# sprite.net
KiCad netlist of a schematic drawn in EAGLE
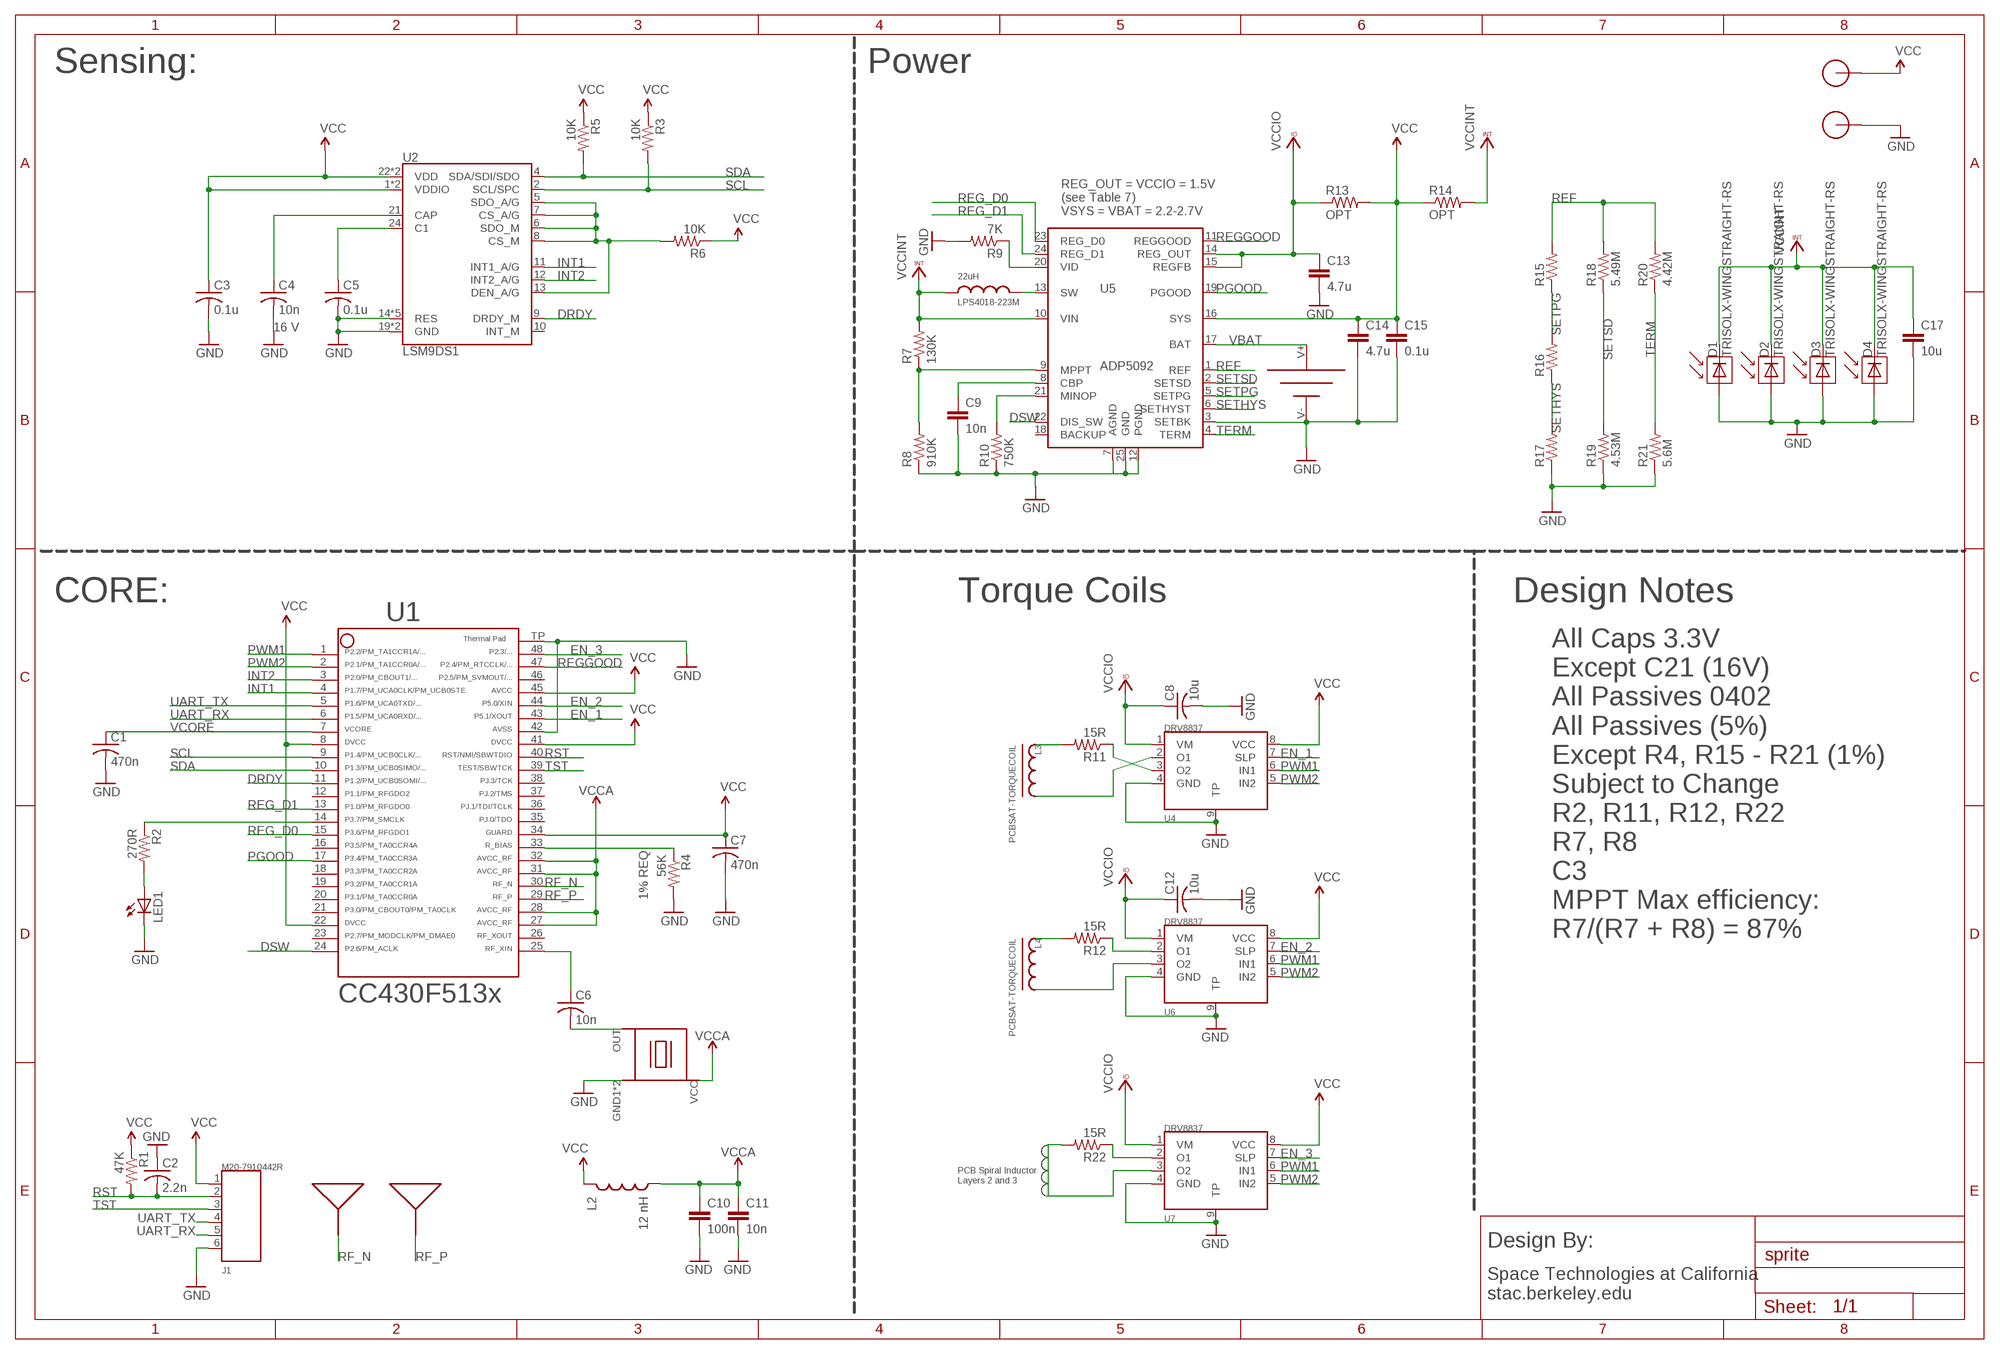
[diagram p0: schematic, sheet 1]

(export (version "E")
  (design (tool "Eeschema 10.0.6"))
  (components
    (comp (ref "A1")
      (value "SPRITEANTENNA_ANTENNA")
      (footprint "eagle-import:SPRITEANTENNA_ANTENNA")
      (libsource (lib "eagle-import") (part "SPRITEANTENNA_ANTENNA"))
    )
    (comp (ref "A2")
      (value "SPRITEANTENNA_ANTENNA")
      (footprint "eagle-import:SPRITEANTENNA_ANTENNA")
      (libsource (lib "eagle-import") (part "SPRITEANTENNA_ANTENNA"))
    )
    (comp (ref "B1")
      (value "UMAC_UMAC")
      (footprint "eagle-import:UMAC_UMAC")
      (libsource (lib "eagle-import") (part "UMAC_UMAC"))
    )
    (comp (ref "C1")
      (value "470n")
      (footprint "eagle-import:C0402")
      (libsource (lib "eagle-import") (part "C-USC0402"))
    )
    (comp (ref "C2")
      (value "2.2n")
      (footprint "eagle-import:C0402")
      (libsource (lib "eagle-import") (part "C-USC0402"))
    )
    (comp (ref "C3")
      (value "0.1u")
      (footprint "eagle-import:C0402")
      (libsource (lib "eagle-import") (part "C-USC0402"))
    )
    (comp (ref "C4")
      (value "10n")
      (footprint "eagle-import:C0402")
      (libsource (lib "eagle-import") (part "C-USC0402"))
    )
    (comp (ref "C5")
      (value "0.1u")
      (footprint "eagle-import:C0402")
      (libsource (lib "eagle-import") (part "C-USC0402"))
    )
    (comp (ref "C6")
      (value "10n")
      (footprint "eagle-import:C0402")
      (libsource (lib "eagle-import") (part "C-USC0402"))
    )
    (comp (ref "C7")
      (value "470n")
      (footprint "eagle-import:C0402")
      (libsource (lib "eagle-import") (part "C-USC0402"))
    )
    (comp (ref "C8")
      (value "10u")
      (footprint "eagle-import:C0402")
      (libsource (lib "eagle-import") (part "C-USC0402"))
    )
    (comp (ref "C9")
      (value "10n")
      (footprint "eagle-import:C0402")
      (libsource (lib "eagle-import") (part "C-EUC0402"))
    )
    (comp (ref "C10")
      (value "100n")
      (footprint "eagle-import:C0402")
      (libsource (lib "eagle-import") (part "C-EUC0402"))
    )
    (comp (ref "C11")
      (value "10n")
      (footprint "eagle-import:C0402")
      (libsource (lib "eagle-import") (part "C-EUC0402"))
    )
    (comp (ref "C12")
      (value "10u")
      (footprint "eagle-import:C0402")
      (libsource (lib "eagle-import") (part "C-USC0402"))
    )
    (comp (ref "C13")
      (value "4.7u")
      (footprint "eagle-import:C0402")
      (libsource (lib "eagle-import") (part "C-EUC0402"))
    )
    (comp (ref "C14")
      (value "4.7u")
      (footprint "eagle-import:C0402")
      (libsource (lib "eagle-import") (part "C-EUC0402"))
    )
    (comp (ref "C15")
      (value "0.1u")
      (footprint "eagle-import:C0402")
      (libsource (lib "eagle-import") (part "C-EUC0402"))
    )
    (comp (ref "C17")
      (value "10u")
      (footprint "eagle-import:C0402")
      (libsource (lib "eagle-import") (part "C-EUC0402"))
    )
    (comp (ref "D1")
      (value "TRISOLX-WINGSTRAIGHT-RS")
      (footprint "eagle-import:TRISOLX-STRAIGHT-RS")
      (libsource (lib "eagle-import") (part "TRISOLX-WINGSTRAIGHT-RS"))
    )
    (comp (ref "D2")
      (value "TRISOLX-WINGSTRAIGHT-RS")
      (footprint "eagle-import:TRISOLX-STRAIGHT-RS")
      (libsource (lib "eagle-import") (part "TRISOLX-WINGSTRAIGHT-RS"))
    )
    (comp (ref "D3")
      (value "TRISOLX-WINGSTRAIGHT-RS")
      (footprint "eagle-import:TRISOLX-STRAIGHT-RS")
      (libsource (lib "eagle-import") (part "TRISOLX-WINGSTRAIGHT-RS"))
    )
    (comp (ref "D4")
      (value "TRISOLX-WINGSTRAIGHT-RS")
      (footprint "eagle-import:TRISOLX-STRAIGHT-RS")
      (libsource (lib "eagle-import") (part "TRISOLX-WINGSTRAIGHT-RS"))
    )
    (comp (ref "J1")
      (value "M20-7910442R")
      (footprint "eagle-import:M20-7910442R")
      (libsource (lib "eagle-import") (part "M20-7910442R"))
    )
    (comp (ref "L1")
      (value "LPS4018-223M")
      (footprint "eagle-import:LPS4018-223M")
      (libsource (lib "eagle-import") (part "LPS4018-223M"))
    )
    (comp (ref "L2")
      (value "12 nH")
      (footprint "eagle-import:0603")
      (libsource (lib "eagle-import") (part "INDUCTOR0603"))
    )
    (comp (ref "L3")
      (value "PCBSAT-TORQUECOIL")
      (footprint "eagle-import:PCBSAT-TORQUECOIL")
      (libsource (lib "eagle-import") (part "PCBSAT-TORQUECOIL"))
    )
    (comp (ref "L4")
      (value "PCBSAT-TORQUECOIL")
      (footprint "eagle-import:PCBSAT-TORQUECOIL")
      (libsource (lib "eagle-import") (part "PCBSAT-TORQUECOIL"))
    )
    (comp (ref "LED1")
      (value "LED0603")
      (footprint "eagle-import:LED-0603")
      (libsource (lib "eagle-import") (part "LED0603"))
    )
    (comp (ref "R1")
      (value "47K")
      (footprint "eagle-import:R0402")
      (libsource (lib "eagle-import") (part "R-US_R0402"))
    )
    (comp (ref "R2")
      (value "270R")
      (footprint "eagle-import:R0402")
      (libsource (lib "eagle-import") (part "R-US_R0402"))
    )
    (comp (ref "R3")
      (value "10K")
      (footprint "eagle-import:R0402")
      (libsource (lib "eagle-import") (part "R-US_R0402"))
    )
    (comp (ref "R4")
      (value "56K")
      (footprint "eagle-import:R0402")
      (libsource (lib "eagle-import") (part "R-US_R0402"))
    )
    (comp (ref "R5")
      (value "10K")
      (footprint "eagle-import:R0402")
      (libsource (lib "eagle-import") (part "R-US_R0402"))
    )
    (comp (ref "R6")
      (value "10K")
      (footprint "eagle-import:R0402")
      (libsource (lib "eagle-import") (part "R-US_R0402"))
    )
    (comp (ref "R7")
      (value "130K")
      (footprint "eagle-import:R0402")
      (libsource (lib "eagle-import") (part "R-US_R0402"))
    )
    (comp (ref "R8")
      (value "910K")
      (footprint "eagle-import:R0402")
      (libsource (lib "eagle-import") (part "R-US_R0402"))
    )
    (comp (ref "R9")
      (value "7K")
      (footprint "eagle-import:R0402")
      (libsource (lib "eagle-import") (part "R-US_R0402"))
    )
    (comp (ref "R10")
      (value "750K")
      (footprint "eagle-import:R0402")
      (libsource (lib "eagle-import") (part "R-US_R0402"))
    )
    (comp (ref "R11")
      (value "15R")
      (footprint "eagle-import:R0402")
      (libsource (lib "eagle-import") (part "R-US_R0402"))
    )
    (comp (ref "R12")
      (value "15R")
      (footprint "eagle-import:R0402")
      (libsource (lib "eagle-import") (part "R-US_R0402"))
    )
    (comp (ref "R13")
      (value "OPT")
      (footprint "eagle-import:R0402")
      (libsource (lib "eagle-import") (part "R-US_R0402"))
    )
    (comp (ref "R14")
      (value "OPT")
      (footprint "eagle-import:R0402")
      (libsource (lib "eagle-import") (part "R-US_R0402"))
    )
    (comp (ref "R15")
      (value "R-US_R0402")
      (footprint "eagle-import:R0402")
      (libsource (lib "eagle-import") (part "R-US_R0402"))
    )
    (comp (ref "R16")
      (value "R-US_R0402")
      (footprint "eagle-import:R0402")
      (libsource (lib "eagle-import") (part "R-US_R0402"))
    )
    (comp (ref "R17")
      (value "R-US_R0402")
      (footprint "eagle-import:R0402")
      (libsource (lib "eagle-import") (part "R-US_R0402"))
    )
    (comp (ref "R18")
      (value "5.49M")
      (footprint "eagle-import:R0402")
      (libsource (lib "eagle-import") (part "R-US_R0402"))
    )
    (comp (ref "R19")
      (value "4.53M")
      (footprint "eagle-import:R0402")
      (libsource (lib "eagle-import") (part "R-US_R0402"))
    )
    (comp (ref "R20")
      (value "4.42M")
      (footprint "eagle-import:R0402")
      (libsource (lib "eagle-import") (part "R-US_R0402"))
    )
    (comp (ref "R21")
      (value "5.6M")
      (footprint "eagle-import:R0402")
      (libsource (lib "eagle-import") (part "R-US_R0402"))
    )
    (comp (ref "R22")
      (value "15R")
      (footprint "eagle-import:R0402")
      (libsource (lib "eagle-import") (part "R-US_R0402"))
    )
    (comp (ref "U1")
      (value "CC430F513X")
      (footprint "eagle-import:TI_MSP430_V16_RGZ48")
      (libsource (lib "eagle-import") (part "CC430F513X"))
    )
    (comp (ref "U2")
      (value "LSM9DS1")
      (footprint "eagle-import:LGA24-8X4")
      (libsource (lib "eagle-import") (part "LSM9DS1"))
    )
    (comp (ref "U3")
      (value "SPRITETCXO_TCXO_7Z")
      (footprint "eagle-import:SPRITETCXO_TXC_7Z")
      (libsource (lib "eagle-import") (part "SPRITETCXO_TCXO_7Z"))
    )
    (comp (ref "U4")
      (value "DRV8837")
      (footprint "eagle-import:SON50P200X200X75-8N")
      (libsource (lib "eagle-import") (part "DRV8837"))
    )
    (comp (ref "U5")
      (value "ADP5092")
      (footprint "eagle-import:QFN50P400X400X100-25N")
      (libsource (lib "eagle-import") (part "ADP5092"))
    )
    (comp (ref "U6")
      (value "DRV8837")
      (footprint "eagle-import:SON50P200X200X75-8N")
      (libsource (lib "eagle-import") (part "DRV8837"))
    )
    (comp (ref "U7")
      (value "DRV8837")
      (footprint "eagle-import:SON50P200X200X75-8N")
      (libsource (lib "eagle-import") (part "DRV8837"))
    )
    (comp (ref "X1")
      (value "SPRITEPIN_SPRITE_PIN")
      (footprint "eagle-import:SPRITEPIN_SPRITE_PIN")
      (libsource (lib "eagle-import") (part "SPRITEPIN_SPRITE_PIN"))
    )
    (comp (ref "X2")
      (value "SPRITEPIN_SPRITE_PIN")
      (footprint "eagle-import:SPRITEPIN_SPRITE_PIN")
      (libsource (lib "eagle-import") (part "SPRITEPIN_SPRITE_PIN"))
    )
  )
  (nets
    (net (code "1") (name "/DRDY") (class "Default")
      (node (ref "U1") (pin "11") (pinfunction "11_11") (pintype "bidirectional"))
      (node (ref "U2") (pin "9") (pinfunction "DRDY_M_9") (pintype "bidirectional"))
    )
    (net (code "2") (name "/DSW") (class "Default")
      (node (ref "U1") (pin "24") (pinfunction "24_24") (pintype "bidirectional"))
      (node (ref "U5") (pin "22") (pinfunction "DIS_SW_22") (pintype "bidirectional"))
    )
    (net (code "3") (name "/EN_1") (class "Default")
      (node (ref "U1") (pin "43") (pinfunction "43_43") (pintype "input"))
      (node (ref "U4") (pin "7") (pinfunction "SLP_7") (pintype "bidirectional"))
    )
    (net (code "4") (name "/EN_2") (class "Default")
      (node (ref "U1") (pin "44") (pinfunction "44_44") (pintype "input"))
      (node (ref "U6") (pin "7") (pinfunction "SLP_7") (pintype "bidirectional"))
    )
    (net (code "5") (name "/EN_3") (class "Default")
      (node (ref "U1") (pin "48") (pinfunction "48_48") (pintype "bidirectional"))
      (node (ref "U7") (pin "7") (pinfunction "SLP_7") (pintype "bidirectional"))
    )
    (net (code "6") (name "/INT1") (class "Default")
      (node (ref "U1") (pin "4") (pinfunction "4_4") (pintype "bidirectional"))
      (node (ref "U2") (pin "11") (pinfunction "INT1_A/G_11") (pintype "bidirectional"))
    )
    (net (code "7") (name "/INT2") (class "Default")
      (node (ref "U1") (pin "3") (pinfunction "3_3") (pintype "bidirectional"))
      (node (ref "U2") (pin "12") (pinfunction "INT2_A/G_12") (pintype "bidirectional"))
    )
    (net (code "8") (name "/PGOOD") (class "Default")
      (node (ref "U1") (pin "17") (pinfunction "17_17") (pintype "bidirectional"))
      (node (ref "U5") (pin "19") (pinfunction "PGOOD_19") (pintype "bidirectional"))
    )
    (net (code "9") (name "/PWM1") (class "Default")
      (node (ref "U1") (pin "1") (pinfunction "1_1") (pintype "bidirectional"))
      (node (ref "U4") (pin "6") (pinfunction "IN1_6") (pintype "bidirectional"))
      (node (ref "U6") (pin "6") (pinfunction "IN1_6") (pintype "bidirectional"))
      (node (ref "U7") (pin "6") (pinfunction "IN1_6") (pintype "bidirectional"))
    )
    (net (code "10") (name "/PWM2") (class "Default")
      (node (ref "U1") (pin "2") (pinfunction "2_2") (pintype "bidirectional"))
      (node (ref "U4") (pin "5") (pinfunction "IN2_5") (pintype "bidirectional"))
      (node (ref "U6") (pin "5") (pinfunction "IN2_5") (pintype "bidirectional"))
      (node (ref "U7") (pin "5") (pinfunction "IN2_5") (pintype "bidirectional"))
    )
    (net (code "11") (name "/REF") (class "Default")
      (node (ref "R15") (pin "2") (pinfunction "2_2") (pintype "passive"))
      (node (ref "R18") (pin "2") (pinfunction "2_2") (pintype "passive"))
      (node (ref "R20") (pin "2") (pinfunction "2_2") (pintype "passive"))
      (node (ref "U5") (pin "1") (pinfunction "REF_1") (pintype "bidirectional"))
    )
    (net (code "12") (name "/REGGOOD") (class "Default")
      (node (ref "U1") (pin "47") (pinfunction "47_47") (pintype "input"))
      (node (ref "U5") (pin "11") (pinfunction "REGGOOD_11") (pintype "bidirectional"))
    )
    (net (code "13") (name "/REG_D0") (class "Default")
      (node (ref "U1") (pin "15") (pinfunction "15_15") (pintype "bidirectional"))
      (node (ref "U5") (pin "23") (pinfunction "REG_D0_23") (pintype "bidirectional"))
    )
    (net (code "14") (name "/REG_D1") (class "Default")
      (node (ref "U1") (pin "13") (pinfunction "13_13") (pintype "bidirectional"))
      (node (ref "U5") (pin "24") (pinfunction "REG_D1_24") (pintype "bidirectional"))
    )
    (net (code "15") (name "/RF_N") (class "Default")
      (node (ref "A1") (pin "IN1") (pinfunction "IN_IN1") (pintype "bidirectional"))
      (node (ref "A1") (pin "IN2") (pinfunction "IN_IN2") (pintype "bidirectional"))
      (node (ref "A1") (pin "IN3") (pinfunction "IN_IN3") (pintype "bidirectional"))
      (node (ref "U1") (pin "30") (pinfunction "30_30") (pintype "bidirectional"))
    )
    (net (code "16") (name "/RF_P") (class "Default")
      (node (ref "A2") (pin "IN1") (pinfunction "IN_IN1") (pintype "bidirectional"))
      (node (ref "A2") (pin "IN2") (pinfunction "IN_IN2") (pintype "bidirectional"))
      (node (ref "A2") (pin "IN3") (pinfunction "IN_IN3") (pintype "bidirectional"))
      (node (ref "U1") (pin "29") (pinfunction "29_29") (pintype "bidirectional"))
    )
    (net (code "17") (name "/RST") (class "Default")
      (node (ref "C2") (pin "2") (pinfunction "2_2") (pintype "passive"))
      (node (ref "J1") (pin "2") (pinfunction "P$2_2") (pintype "bidirectional"))
      (node (ref "R1") (pin "2") (pinfunction "2_2") (pintype "passive"))
      (node (ref "U1") (pin "40") (pinfunction "40_40") (pintype "bidirectional"))
    )
    (net (code "18") (name "/SCL") (class "Default")
      (node (ref "R3") (pin "2") (pinfunction "2_2") (pintype "passive"))
      (node (ref "U1") (pin "9") (pinfunction "9_9") (pintype "bidirectional"))
      (node (ref "U2") (pin "2") (pinfunction "SCL/SPC_2") (pintype "bidirectional"))
    )
    (net (code "19") (name "/SDA") (class "Default")
      (node (ref "R5") (pin "2") (pinfunction "2_2") (pintype "passive"))
      (node (ref "U1") (pin "10") (pinfunction "10_10") (pintype "bidirectional"))
      (node (ref "U2") (pin "4") (pinfunction "SDA/SDI/SDO_4") (pintype "bidirectional"))
    )
    (net (code "20") (name "/SETHYS") (class "Default")
      (node (ref "R16") (pin "1") (pinfunction "1_1") (pintype "passive"))
      (node (ref "R17") (pin "2") (pinfunction "2_2") (pintype "passive"))
      (node (ref "U5") (pin "6") (pinfunction "SETHYST_6") (pintype "bidirectional"))
    )
    (net (code "21") (name "/SETPG") (class "Default")
      (node (ref "R15") (pin "1") (pinfunction "1_1") (pintype "passive"))
      (node (ref "R16") (pin "2") (pinfunction "2_2") (pintype "passive"))
      (node (ref "U5") (pin "5") (pinfunction "SETPG_5") (pintype "bidirectional"))
    )
    (net (code "22") (name "/SETSD") (class "Default")
      (node (ref "R18") (pin "1") (pinfunction "1_1") (pintype "passive"))
      (node (ref "R19") (pin "2") (pinfunction "2_2") (pintype "passive"))
      (node (ref "U5") (pin "2") (pinfunction "SETSD_2") (pintype "bidirectional"))
    )
    (net (code "23") (name "/TERM") (class "Default")
      (node (ref "R20") (pin "1") (pinfunction "1_1") (pintype "passive"))
      (node (ref "R21") (pin "2") (pinfunction "2_2") (pintype "passive"))
      (node (ref "U5") (pin "4") (pinfunction "TERM_4") (pintype "bidirectional"))
    )
    (net (code "24") (name "/TST") (class "Default")
      (node (ref "J1") (pin "3") (pinfunction "P$3_3") (pintype "bidirectional"))
      (node (ref "U1") (pin "39") (pinfunction "39_39") (pintype "input"))
    )
    (net (code "25") (name "/UART_RX") (class "Default")
      (node (ref "J1") (pin "5") (pinfunction "P$5_5") (pintype "bidirectional"))
      (node (ref "U1") (pin "6") (pinfunction "6_6") (pintype "bidirectional"))
    )
    (net (code "26") (name "/UART_TX") (class "Default")
      (node (ref "J1") (pin "4") (pinfunction "P$4_4") (pintype "bidirectional"))
      (node (ref "U1") (pin "5") (pinfunction "5_5") (pintype "bidirectional"))
    )
    (net (code "27") (name "/VBAT") (class "Default")
      (node (ref "B1") (pin "V+") (pinfunction "V+_V+") (pintype "power_in"))
      (node (ref "U5") (pin "17") (pinfunction "BAT_17") (pintype "bidirectional"))
    )
    (net (code "28") (name "/VCORE") (class "Default")
      (node (ref "C1") (pin "1") (pinfunction "1_1") (pintype "passive"))
      (node (ref "U1") (pin "7") (pinfunction "7_7") (pintype "power_in"))
    )
    (net (code "29") (name "GND") (class "Default")
      (node (ref "B1") (pin "V-") (pinfunction "V-_V-") (pintype "power_in"))
      (node (ref "C1") (pin "2") (pinfunction "2_2") (pintype "passive"))
      (node (ref "C10") (pin "2") (pinfunction "2_2") (pintype "passive"))
      (node (ref "C11") (pin "2") (pinfunction "2_2") (pintype "passive"))
      (node (ref "C12") (pin "2") (pinfunction "2_2") (pintype "passive"))
      (node (ref "C13") (pin "2") (pinfunction "2_2") (pintype "passive"))
      (node (ref "C14") (pin "2") (pinfunction "2_2") (pintype "passive"))
      (node (ref "C15") (pin "2") (pinfunction "2_2") (pintype "passive"))
      (node (ref "C17") (pin "2") (pinfunction "2_2") (pintype "passive"))
      (node (ref "C2") (pin "1") (pinfunction "1_1") (pintype "passive"))
      (node (ref "C3") (pin "2") (pinfunction "2_2") (pintype "passive"))
      (node (ref "C4") (pin "2") (pinfunction "2_2") (pintype "passive"))
      (node (ref "C5") (pin "2") (pinfunction "2_2") (pintype "passive"))
      (node (ref "C7") (pin "2") (pinfunction "2_2") (pintype "passive"))
      (node (ref "C8") (pin "2") (pinfunction "2_2") (pintype "passive"))
      (node (ref "C9") (pin "2") (pinfunction "2_2") (pintype "passive"))
      (node (ref "D1") (pin "P$1") (pinfunction "A_P$1") (pintype "passive"))
      (node (ref "D2") (pin "P$1") (pinfunction "A_P$1") (pintype "passive"))
      (node (ref "D3") (pin "P$1") (pinfunction "A_P$1") (pintype "passive"))
      (node (ref "D4") (pin "P$1") (pinfunction "A_P$1") (pintype "passive"))
      (node (ref "J1") (pin "6") (pinfunction "P$6_6") (pintype "bidirectional"))
      (node (ref "LED1") (pin "C") (pinfunction "C_C") (pintype "passive"))
      (node (ref "R10") (pin "1") (pinfunction "1_1") (pintype "passive"))
      (node (ref "R17") (pin "1") (pinfunction "1_1") (pintype "passive"))
      (node (ref "R19") (pin "1") (pinfunction "1_1") (pintype "passive"))
      (node (ref "R21") (pin "1") (pinfunction "1_1") (pintype "passive"))
      (node (ref "R4") (pin "2") (pinfunction "2_2") (pintype "passive"))
      (node (ref "R8") (pin "1") (pinfunction "1_1") (pintype "passive"))
      (node (ref "R9") (pin "2") (pinfunction "2_2") (pintype "passive"))
      (node (ref "U1") (pin "42") (pinfunction "42_42") (pintype "power_in"))
      (node (ref "U1") (pin "TP") (pinfunction "49_TP") (pintype "power_in"))
      (node (ref "U2") (pin "14") (pinfunction "RES_14") (pintype "bidirectional"))
      (node (ref "U2") (pin "15") (pinfunction "RES_15") (pintype "bidirectional"))
      (node (ref "U2") (pin "16") (pinfunction "RES_16") (pintype "bidirectional"))
      (node (ref "U2") (pin "17") (pinfunction "RES_17") (pintype "bidirectional"))
      (node (ref "U2") (pin "18") (pinfunction "RES_18") (pintype "bidirectional"))
      (node (ref "U2") (pin "19") (pinfunction "GND_19") (pintype "bidirectional"))
      (node (ref "U2") (pin "20") (pinfunction "GND_20") (pintype "bidirectional"))
      (node (ref "U3") (pin "GND1") (pinfunction "GND_GND1") (pintype "bidirectional"))
      (node (ref "U3") (pin "GND2") (pinfunction "GND_GND2") (pintype "bidirectional"))
      (node (ref "U4") (pin "4") (pinfunction "GND_4") (pintype "bidirectional"))
      (node (ref "U4") (pin "9") (pinfunction "TP_9") (pintype "bidirectional"))
      (node (ref "U5") (pin "12") (pinfunction "PGND_12") (pintype "bidirectional"))
      (node (ref "U5") (pin "25") (pinfunction "GND_25") (pintype "bidirectional"))
      (node (ref "U5") (pin "3") (pinfunction "SETBK_3") (pintype "bidirectional"))
      (node (ref "U5") (pin "7") (pinfunction "AGND_7") (pintype "bidirectional"))
      (node (ref "U6") (pin "4") (pinfunction "GND_4") (pintype "bidirectional"))
      (node (ref "U6") (pin "9") (pinfunction "TP_9") (pintype "bidirectional"))
      (node (ref "U7") (pin "4") (pinfunction "GND_4") (pintype "bidirectional"))
      (node (ref "U7") (pin "9") (pinfunction "TP_9") (pintype "bidirectional"))
      (node (ref "X2") (pin "PIN") (pinfunction "PIN_PIN") (pintype "bidirectional"))
    )
    (net (code "30") (name "Net-(C6-Pad1)") (class "Default")
      (node (ref "C6") (pin "1") (pinfunction "1_1") (pintype "passive"))
      (node (ref "U1") (pin "25") (pinfunction "25_25") (pintype "input"))
    )
    (net (code "31") (name "Net-(C6-Pad2)") (class "Default")
      (node (ref "C6") (pin "2") (pinfunction "2_2") (pintype "passive"))
      (node (ref "U3") (pin "OUT") (pinfunction "OUT_OUT") (pintype "bidirectional"))
    )
    (net (code "32") (name "Net-(L3-P$1)") (class "Default")
      (node (ref "L3") (pin "1") (pinfunction "P$1_1") (pintype "bidirectional"))
      (node (ref "R11") (pin "2") (pinfunction "2_2") (pintype "passive"))
    )
    (net (code "33") (name "Net-(L3-P$2)") (class "Default")
      (node (ref "L3") (pin "2") (pinfunction "P$2_2") (pintype "bidirectional"))
      (node (ref "U4") (pin "2") (pinfunction "O1_2") (pintype "bidirectional"))
    )
    (net (code "34") (name "Net-(L4-P$1)") (class "Default")
      (node (ref "L4") (pin "1") (pinfunction "P$1_1") (pintype "bidirectional"))
      (node (ref "R12") (pin "2") (pinfunction "2_2") (pintype "passive"))
    )
    (net (code "35") (name "Net-(L4-P$2)") (class "Default")
      (node (ref "L4") (pin "2") (pinfunction "P$2_2") (pintype "bidirectional"))
      (node (ref "U6") (pin "3") (pinfunction "O2_3") (pintype "bidirectional"))
    )
    (net (code "36") (name "Net-(LED1-PadA)") (class "Default")
      (node (ref "LED1") (pin "A") (pinfunction "A_A") (pintype "passive"))
      (node (ref "R2") (pin "2") (pinfunction "2_2") (pintype "passive"))
    )
    (net (code "37") (name "Net-(R2-Pad1)") (class "Default")
      (node (ref "R2") (pin "1") (pinfunction "1_1") (pintype "passive"))
      (node (ref "U1") (pin "14") (pinfunction "14_14") (pintype "bidirectional"))
    )
    (net (code "38") (name "Net-(R4-Pad1)") (class "Default")
      (node (ref "R4") (pin "1") (pinfunction "1_1") (pintype "passive"))
      (node (ref "U1") (pin "33") (pinfunction "33_33") (pintype "power_in"))
    )
    (net (code "39") (name "Net-(U2-C1)") (class "Default")
      (node (ref "C5") (pin "1") (pinfunction "1_1") (pintype "passive"))
      (node (ref "U2") (pin "24") (pinfunction "C1_24") (pintype "bidirectional"))
    )
    (net (code "40") (name "Net-(U2-CAP)") (class "Default")
      (node (ref "C4") (pin "1") (pinfunction "1_1") (pintype "passive"))
      (node (ref "U2") (pin "21") (pinfunction "CAP_21") (pintype "bidirectional"))
    )
    (net (code "41") (name "Net-(U2-CS_A{slash}G)") (class "Default")
      (node (ref "R6") (pin "2") (pinfunction "2_2") (pintype "passive"))
      (node (ref "U2") (pin "13") (pinfunction "DEN_A/G_13") (pintype "bidirectional"))
      (node (ref "U2") (pin "5") (pinfunction "SDO_A/G_5") (pintype "bidirectional"))
      (node (ref "U2") (pin "6") (pinfunction "SDO_M_6") (pintype "bidirectional"))
      (node (ref "U2") (pin "7") (pinfunction "CS_A/G_7") (pintype "bidirectional"))
      (node (ref "U2") (pin "8") (pinfunction "CS_M_8") (pintype "bidirectional"))
    )
    (net (code "42") (name "Net-(U4-O2)") (class "Default")
      (node (ref "R11") (pin "1") (pinfunction "1_1") (pintype "passive"))
      (node (ref "U4") (pin "3") (pinfunction "O2_3") (pintype "bidirectional"))
    )
    (net (code "43") (name "Net-(U5-CBP)") (class "Default")
      (node (ref "C9") (pin "1") (pinfunction "1_1") (pintype "passive"))
      (node (ref "U5") (pin "8") (pinfunction "CBP_8") (pintype "bidirectional"))
    )
    (net (code "44") (name "Net-(U5-MINOP)") (class "Default")
      (node (ref "R10") (pin "2") (pinfunction "2_2") (pintype "passive"))
      (node (ref "U5") (pin "21") (pinfunction "MINOP_21") (pintype "bidirectional"))
    )
    (net (code "45") (name "Net-(U5-MPPT)") (class "Default")
      (node (ref "R7") (pin "1") (pinfunction "1_1") (pintype "passive"))
      (node (ref "R8") (pin "2") (pinfunction "2_2") (pintype "passive"))
      (node (ref "U5") (pin "9") (pinfunction "MPPT_9") (pintype "bidirectional"))
    )
    (net (code "46") (name "Net-(U5-SW)") (class "Default")
      (node (ref "L1") (pin "P$2") (pinfunction "P$2_P$2") (pintype "bidirectional"))
      (node (ref "U5") (pin "13") (pinfunction "SW_13") (pintype "bidirectional"))
    )
    (net (code "47") (name "Net-(U5-VID)") (class "Default")
      (node (ref "R9") (pin "1") (pinfunction "1_1") (pintype "passive"))
      (node (ref "U5") (pin "20") (pinfunction "VID_20") (pintype "bidirectional"))
    )
    (net (code "48") (name "Net-(U6-O1)") (class "Default")
      (node (ref "R12") (pin "1") (pinfunction "1_1") (pintype "passive"))
      (node (ref "U6") (pin "2") (pinfunction "O1_2") (pintype "bidirectional"))
    )
    (net (code "49") (name "Net-(U7-O1)") (class "Default")
      (node (ref "R22") (pin "1") (pinfunction "1_1") (pintype "passive"))
      (node (ref "U7") (pin "2") (pinfunction "O1_2") (pintype "bidirectional"))
    )
    (net (code "50") (name "Net-(U7-O2)") (class "Default")
      (node (ref "R22") (pin "2") (pinfunction "2_2") (pintype "passive"))
      (node (ref "U7") (pin "3") (pinfunction "O2_3") (pintype "bidirectional"))
    )
    (net (code "51") (name "VCC") (class "Default")
      (node (ref "C14") (pin "1") (pinfunction "1_1") (pintype "passive"))
      (node (ref "C15") (pin "1") (pinfunction "1_1") (pintype "passive"))
      (node (ref "C3") (pin "1") (pinfunction "1_1") (pintype "passive"))
      (node (ref "C7") (pin "1") (pinfunction "1_1") (pintype "passive"))
      (node (ref "J1") (pin "1") (pinfunction "P$1_1") (pintype "bidirectional"))
      (node (ref "L2") (pin "1") (pinfunction "1_1") (pintype "passive"))
      (node (ref "R1") (pin "1") (pinfunction "1_1") (pintype "passive"))
      (node (ref "R13") (pin "2") (pinfunction "2_2") (pintype "passive"))
      (node (ref "R14") (pin "1") (pinfunction "1_1") (pintype "passive"))
      (node (ref "R3") (pin "1") (pinfunction "1_1") (pintype "passive"))
      (node (ref "R5") (pin "1") (pinfunction "1_1") (pintype "passive"))
      (node (ref "R6") (pin "1") (pinfunction "1_1") (pintype "passive"))
      (node (ref "U1") (pin "22") (pinfunction "22_22") (pintype "power_in"))
      (node (ref "U1") (pin "34") (pinfunction "34_34") (pintype "power_in"))
      (node (ref "U1") (pin "41") (pinfunction "41_41") (pintype "power_in"))
      (node (ref "U1") (pin "45") (pinfunction "45_45") (pintype "input"))
      (node (ref "U1") (pin "8") (pinfunction "8_8") (pintype "power_in"))
      (node (ref "U2") (pin "1") (pinfunction "VDDIO_1") (pintype "bidirectional"))
      (node (ref "U2") (pin "22") (pinfunction "VDD_22") (pintype "bidirectional"))
      (node (ref "U2") (pin "23") (pinfunction "VDD_23") (pintype "bidirectional"))
      (node (ref "U2") (pin "3") (pinfunction "VDDIO_3") (pintype "bidirectional"))
      (node (ref "U4") (pin "8") (pinfunction "VCC_8") (pintype "bidirectional"))
      (node (ref "U5") (pin "16") (pinfunction "SYS_16") (pintype "bidirectional"))
      (node (ref "U6") (pin "8") (pinfunction "VCC_8") (pintype "bidirectional"))
      (node (ref "U7") (pin "8") (pinfunction "VCC_8") (pintype "bidirectional"))
      (node (ref "X1") (pin "PIN") (pinfunction "PIN_PIN") (pintype "bidirectional"))
    )
    (net (code "52") (name "VCCA") (class "Default")
      (node (ref "C10") (pin "1") (pinfunction "1_1") (pintype "passive"))
      (node (ref "C11") (pin "1") (pinfunction "1_1") (pintype "passive"))
      (node (ref "L2") (pin "2") (pinfunction "2_2") (pintype "passive"))
      (node (ref "U1") (pin "27") (pinfunction "27_27") (pintype "power_in"))
      (node (ref "U1") (pin "28") (pinfunction "28_28") (pintype "bidirectional"))
      (node (ref "U1") (pin "31") (pinfunction "31_31") (pintype "power_in"))
      (node (ref "U1") (pin "32") (pinfunction "32_32") (pintype "power_in"))
      (node (ref "U3") (pin "VCC") (pinfunction "VCC_VCC") (pintype "bidirectional"))
    )
    (net (code "53") (name "VCCINT") (class "Default")
      (node (ref "C17") (pin "1") (pinfunction "1_1") (pintype "passive"))
      (node (ref "D1") (pin "P$2") (pinfunction "C_P$2") (pintype "passive"))
      (node (ref "D2") (pin "P$2") (pinfunction "C_P$2") (pintype "passive"))
      (node (ref "D3") (pin "P$2") (pinfunction "C_P$2") (pintype "passive"))
      (node (ref "D4") (pin "P$2") (pinfunction "C_P$2") (pintype "passive"))
      (node (ref "L1") (pin "P$1") (pinfunction "P$1_P$1") (pintype "bidirectional"))
      (node (ref "R14") (pin "2") (pinfunction "2_2") (pintype "passive"))
      (node (ref "R7") (pin "2") (pinfunction "2_2") (pintype "passive"))
      (node (ref "U5") (pin "10") (pinfunction "VIN_10") (pintype "bidirectional"))
    )
    (net (code "54") (name "VCCIO") (class "Default")
      (node (ref "C12") (pin "1") (pinfunction "1_1") (pintype "passive"))
      (node (ref "C13") (pin "1") (pinfunction "1_1") (pintype "passive"))
      (node (ref "C8") (pin "1") (pinfunction "1_1") (pintype "passive"))
      (node (ref "R13") (pin "1") (pinfunction "1_1") (pintype "passive"))
      (node (ref "U4") (pin "1") (pinfunction "VM_1") (pintype "bidirectional"))
      (node (ref "U5") (pin "14") (pinfunction "REG_OUT_14") (pintype "bidirectional"))
      (node (ref "U5") (pin "15") (pinfunction "REGFB_15") (pintype "bidirectional"))
      (node (ref "U6") (pin "1") (pinfunction "VM_1") (pintype "bidirectional"))
      (node (ref "U7") (pin "1") (pinfunction "VM_1") (pintype "bidirectional"))
    )
    (net (code "55") (name "unconnected-(U1-Pad12)") (class "Default")
      (node (ref "U1") (pin "12") (pinfunction "12_12") (pintype "bidirectional"))
    )
    (net (code "56") (name "unconnected-(U1-Pad16)") (class "Default")
      (node (ref "U1") (pin "16") (pinfunction "16_16") (pintype "bidirectional"))
    )
    (net (code "57") (name "unconnected-(U1-Pad18)") (class "Default")
      (node (ref "U1") (pin "18") (pinfunction "18_18") (pintype "bidirectional"))
    )
    (net (code "58") (name "unconnected-(U1-Pad19)") (class "Default")
      (node (ref "U1") (pin "19") (pinfunction "19_19") (pintype "bidirectional"))
    )
    (net (code "59") (name "unconnected-(U1-Pad20)") (class "Default")
      (node (ref "U1") (pin "20") (pinfunction "20_20") (pintype "bidirectional"))
    )
    (net (code "60") (name "unconnected-(U1-Pad21)") (class "Default")
      (node (ref "U1") (pin "21") (pinfunction "21_21") (pintype "bidirectional"))
    )
    (net (code "61") (name "unconnected-(U1-Pad23)") (class "Default")
      (node (ref "U1") (pin "23") (pinfunction "23_23") (pintype "bidirectional"))
    )
    (net (code "62") (name "unconnected-(U1-Pad26)") (class "Default")
      (node (ref "U1") (pin "26") (pinfunction "26_26") (pintype "output"))
    )
    (net (code "63") (name "unconnected-(U1-Pad35)") (class "Default")
      (node (ref "U1") (pin "35") (pinfunction "35_35") (pintype "bidirectional"))
    )
    (net (code "64") (name "unconnected-(U1-Pad36)") (class "Default")
      (node (ref "U1") (pin "36") (pinfunction "36_36") (pintype "bidirectional"))
    )
    (net (code "65") (name "unconnected-(U1-Pad37)") (class "Default")
      (node (ref "U1") (pin "37") (pinfunction "37_37") (pintype "bidirectional"))
    )
    (net (code "66") (name "unconnected-(U1-Pad38)") (class "Default")
      (node (ref "U1") (pin "38") (pinfunction "38_38") (pintype "bidirectional"))
    )
    (net (code "67") (name "unconnected-(U1-Pad46)") (class "Default")
      (node (ref "U1") (pin "46") (pinfunction "46_46") (pintype "bidirectional"))
    )
    (net (code "68") (name "unconnected-(U2-INT_M-Pad10)") (class "Default")
      (node (ref "U2") (pin "10") (pinfunction "INT_M_10") (pintype "bidirectional"))
    )
    (net (code "69") (name "unconnected-(U5-BACKUP-Pad18)") (class "Default")
      (node (ref "U5") (pin "18") (pinfunction "BACKUP_18") (pintype "bidirectional"))
    )
  )
)
